# gateway.net
KiCad netlist of a schematic drawn in EAGLE
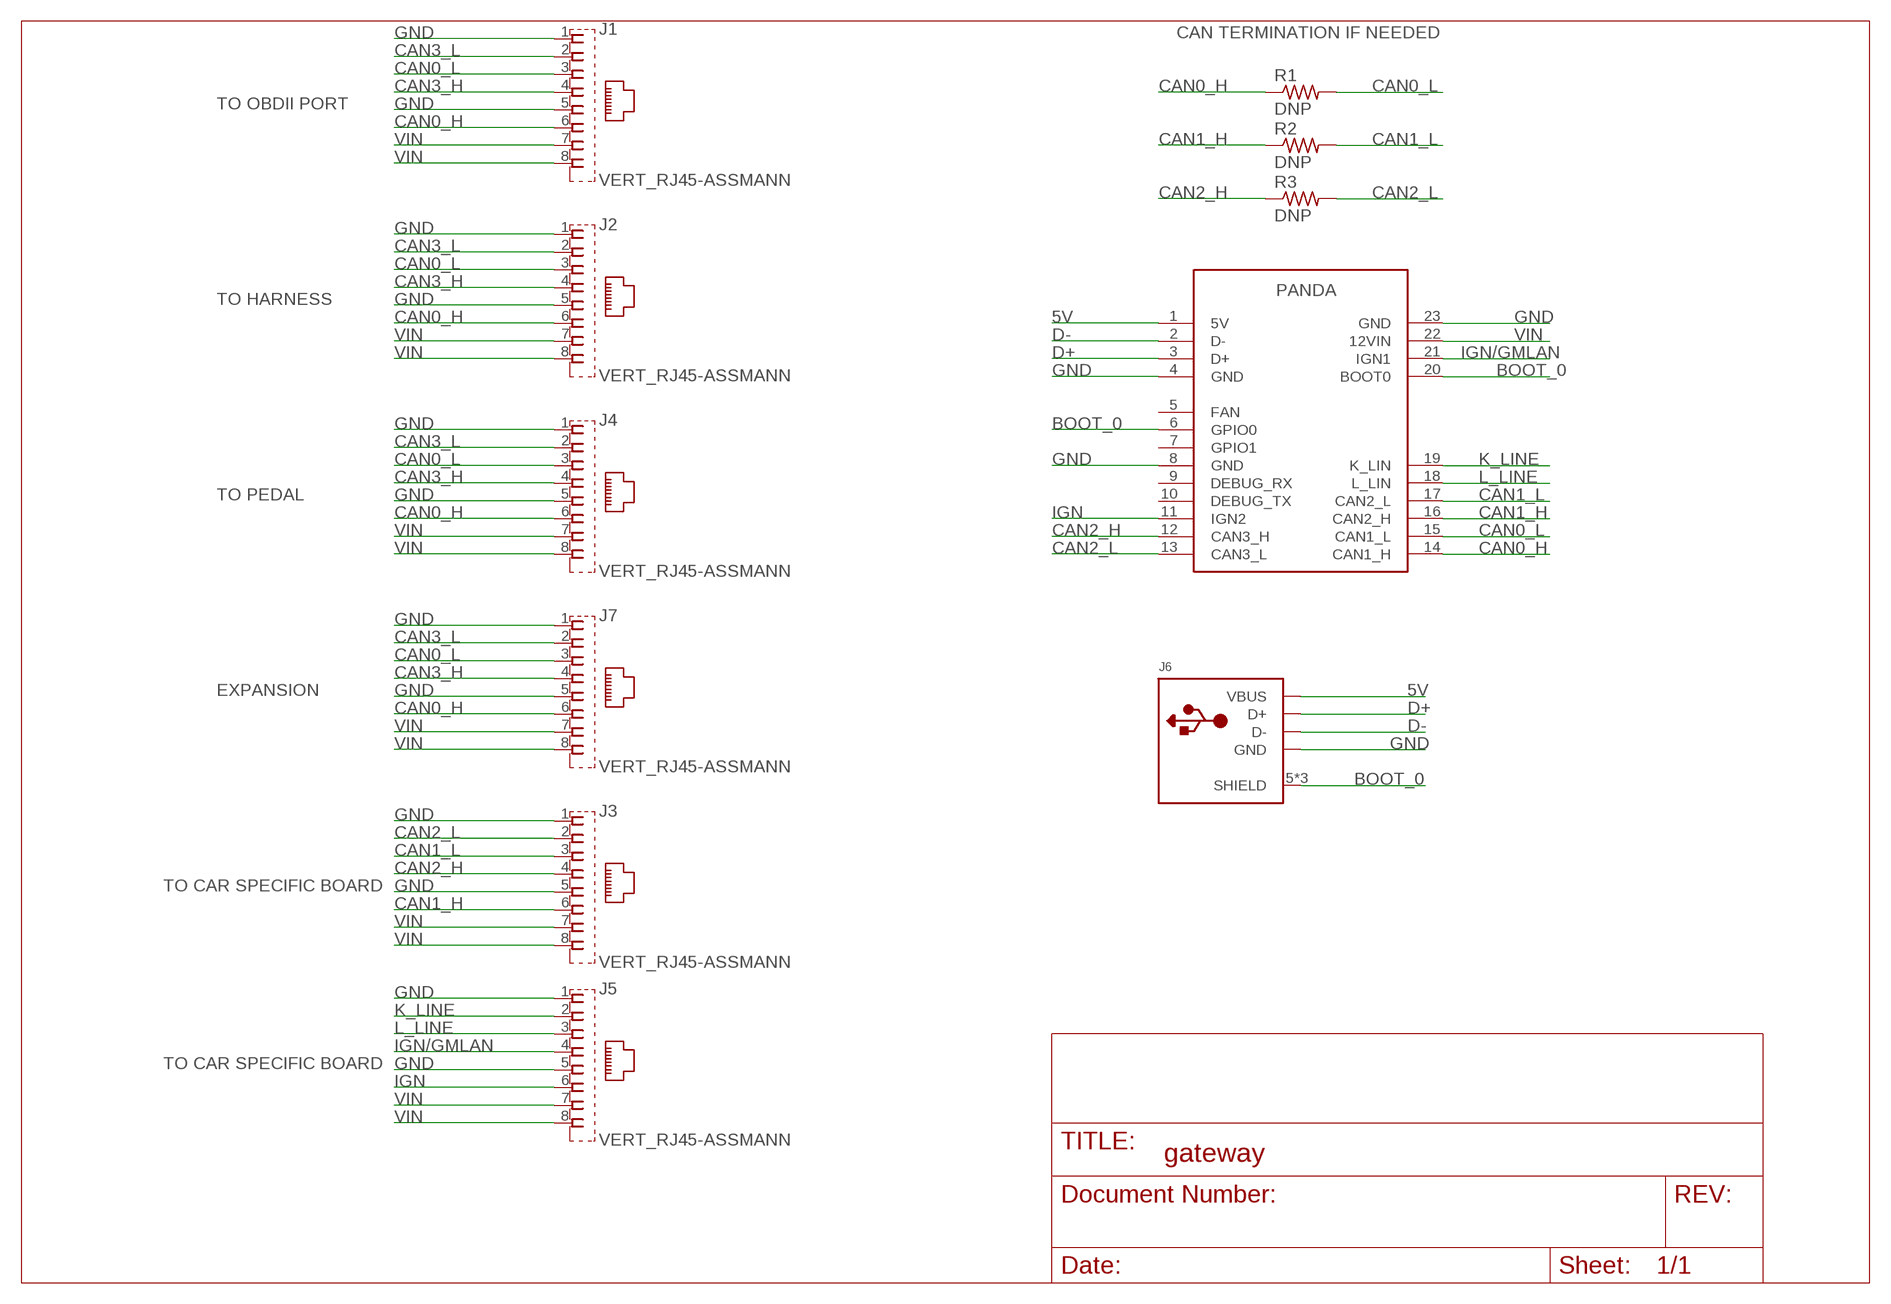
[diagram p0: schematic, sheet 1]

(export (version "E")
  (design (tool "Eeschema 10.0.6"))
  (components
    (comp (ref "J1")
      (value "VERT_RJ45-ASSMANN")
      (footprint "eagle-import:RJ45-VERT")
      (fields (field (name "MPN") "A-2004-2-4-LPS-N-R"))
      (libsource (lib "eagle-import") (part "VERT_RJ45-ASSMANN"))
    )
    (comp (ref "J2")
      (value "VERT_RJ45-ASSMANN")
      (footprint "eagle-import:RJ45-VERT")
      (fields (field (name "MPN") "A-2004-2-4-LPS-N-R"))
      (libsource (lib "eagle-import") (part "VERT_RJ45-ASSMANN"))
    )
    (comp (ref "J3")
      (value "VERT_RJ45-ASSMANN")
      (footprint "eagle-import:RJ45-VERT")
      (fields (field (name "MPN") "A-2004-2-4-LPS-N-R"))
      (libsource (lib "eagle-import") (part "VERT_RJ45-ASSMANN"))
    )
    (comp (ref "J4")
      (value "VERT_RJ45-ASSMANN")
      (footprint "eagle-import:RJ45-VERT")
      (fields (field (name "MPN") "A-2004-2-4-LPS-N-R"))
      (libsource (lib "eagle-import") (part "VERT_RJ45-ASSMANN"))
    )
    (comp (ref "J5")
      (value "VERT_RJ45-ASSMANN")
      (footprint "eagle-import:RJ45-VERT")
      (fields (field (name "MPN") "A-2004-2-4-LPS-N-R"))
      (libsource (lib "eagle-import") (part "VERT_RJ45-ASSMANN"))
    )
    (comp (ref "J6")
      (value "USB-AMOLEX")
      (footprint "eagle-import:USB-A-VERT-MOLEX")
      (fields (field (name "MPN") "1050570001"))
      (libsource (lib "eagle-import") (part "USB-AMOLEX"))
    )
    (comp (ref "J7")
      (value "VERT_RJ45-ASSMANN")
      (footprint "eagle-import:RJ45-VERT")
      (fields (field (name "MPN") "A-2004-2-4-LPS-N-R"))
      (libsource (lib "eagle-import") (part "VERT_RJ45-ASSMANN"))
    )
    (comp (ref "R1")
      (value "DNP")
      (footprint "eagle-import:0603-R")
      (libsource (lib "eagle-import") (part "R0603"))
    )
    (comp (ref "R2")
      (value "DNP")
      (footprint "eagle-import:0603-R")
      (libsource (lib "eagle-import") (part "R0603"))
    )
    (comp (ref "R3")
      (value "DNP")
      (footprint "eagle-import:0603-R")
      (libsource (lib "eagle-import") (part "R0603"))
    )
    (comp (ref "U$1")
      (value "PANDA")
      (footprint "eagle-import:PANDA-FOOT")
      (libsource (lib "eagle-import") (part "PANDA"))
    )
  )
  (nets
    (net (code "1") (name "/5V") (class "Default")
      (node (ref "J6") (pin "1") (pinfunction "VBUS_1") (pintype "power_in"))
      (node (ref "U$1") (pin "1") (pinfunction "5V_1") (pintype "bidirectional"))
    )
    (net (code "2") (name "/BOOT_0") (class "Default")
      (node (ref "J6") (pin "5") (pinfunction "SHIELD_5") (pintype "bidirectional"))
      (node (ref "J6") (pin "6") (pinfunction "SHIELD_6") (pintype "bidirectional"))
      (node (ref "J6") (pin "7") (pinfunction "SHIELD_7") (pintype "bidirectional"))
      (node (ref "U$1") (pin "20") (pinfunction "BOOT0_20") (pintype "bidirectional"))
      (node (ref "U$1") (pin "6") (pinfunction "GPIO0_6") (pintype "bidirectional"))
    )
    (net (code "3") (name "/CAN0_H") (class "Default")
      (node (ref "J1") (pin "6") (pinfunction "6_6") (pintype "passive"))
      (node (ref "J2") (pin "6") (pinfunction "6_6") (pintype "passive"))
      (node (ref "J4") (pin "6") (pinfunction "6_6") (pintype "passive"))
      (node (ref "J7") (pin "6") (pinfunction "6_6") (pintype "passive"))
      (node (ref "R1") (pin "1") (pinfunction "1_1") (pintype "passive"))
      (node (ref "U$1") (pin "14") (pinfunction "CAN1_H_14") (pintype "bidirectional"))
    )
    (net (code "4") (name "/CAN0_L") (class "Default")
      (node (ref "J1") (pin "3") (pinfunction "3_3") (pintype "passive"))
      (node (ref "J2") (pin "3") (pinfunction "3_3") (pintype "passive"))
      (node (ref "J4") (pin "3") (pinfunction "3_3") (pintype "passive"))
      (node (ref "J7") (pin "3") (pinfunction "3_3") (pintype "passive"))
      (node (ref "R1") (pin "2") (pinfunction "2_2") (pintype "passive"))
      (node (ref "U$1") (pin "15") (pinfunction "CAN1_L_15") (pintype "bidirectional"))
    )
    (net (code "5") (name "/CAN1_H") (class "Default")
      (node (ref "J3") (pin "6") (pinfunction "6_6") (pintype "passive"))
      (node (ref "R2") (pin "1") (pinfunction "1_1") (pintype "passive"))
      (node (ref "U$1") (pin "16") (pinfunction "CAN2_H_16") (pintype "bidirectional"))
    )
    (net (code "6") (name "/CAN1_L") (class "Default")
      (node (ref "J3") (pin "3") (pinfunction "3_3") (pintype "passive"))
      (node (ref "R2") (pin "2") (pinfunction "2_2") (pintype "passive"))
      (node (ref "U$1") (pin "17") (pinfunction "CAN2_L_17") (pintype "bidirectional"))
    )
    (net (code "7") (name "/CAN2_H") (class "Default")
      (node (ref "J3") (pin "4") (pinfunction "4_4") (pintype "passive"))
      (node (ref "R3") (pin "1") (pinfunction "1_1") (pintype "passive"))
      (node (ref "U$1") (pin "12") (pinfunction "CAN3_H_12") (pintype "bidirectional"))
    )
    (net (code "8") (name "/CAN2_L") (class "Default")
      (node (ref "J3") (pin "2") (pinfunction "2_2") (pintype "passive"))
      (node (ref "R3") (pin "2") (pinfunction "2_2") (pintype "passive"))
      (node (ref "U$1") (pin "13") (pinfunction "CAN3_L_13") (pintype "bidirectional"))
    )
    (net (code "9") (name "/CAN3_H") (class "Default")
      (node (ref "J1") (pin "4") (pinfunction "4_4") (pintype "passive"))
      (node (ref "J2") (pin "4") (pinfunction "4_4") (pintype "passive"))
      (node (ref "J4") (pin "4") (pinfunction "4_4") (pintype "passive"))
      (node (ref "J7") (pin "4") (pinfunction "4_4") (pintype "passive"))
    )
    (net (code "10") (name "/CAN3_L") (class "Default")
      (node (ref "J1") (pin "2") (pinfunction "2_2") (pintype "passive"))
      (node (ref "J2") (pin "2") (pinfunction "2_2") (pintype "passive"))
      (node (ref "J4") (pin "2") (pinfunction "2_2") (pintype "passive"))
      (node (ref "J7") (pin "2") (pinfunction "2_2") (pintype "passive"))
    )
    (net (code "11") (name "/D+") (class "Default")
      (node (ref "J6") (pin "3") (pinfunction "D+_3") (pintype "bidirectional"))
      (node (ref "U$1") (pin "3") (pinfunction "D+_3") (pintype "bidirectional"))
    )
    (net (code "12") (name "/D-") (class "Default")
      (node (ref "J6") (pin "2") (pinfunction "D-_2") (pintype "bidirectional"))
      (node (ref "U$1") (pin "2") (pinfunction "D-_2") (pintype "bidirectional"))
    )
    (net (code "13") (name "/GND") (class "Default")
      (node (ref "J1") (pin "1") (pinfunction "1_1") (pintype "passive"))
      (node (ref "J1") (pin "5") (pinfunction "5_5") (pintype "passive"))
      (node (ref "J2") (pin "1") (pinfunction "1_1") (pintype "passive"))
      (node (ref "J2") (pin "5") (pinfunction "5_5") (pintype "passive"))
      (node (ref "J3") (pin "1") (pinfunction "1_1") (pintype "passive"))
      (node (ref "J3") (pin "5") (pinfunction "5_5") (pintype "passive"))
      (node (ref "J4") (pin "1") (pinfunction "1_1") (pintype "passive"))
      (node (ref "J4") (pin "5") (pinfunction "5_5") (pintype "passive"))
      (node (ref "J5") (pin "1") (pinfunction "1_1") (pintype "passive"))
      (node (ref "J5") (pin "5") (pinfunction "5_5") (pintype "passive"))
      (node (ref "J6") (pin "4") (pinfunction "GND_4") (pintype "power_in"))
      (node (ref "J7") (pin "1") (pinfunction "1_1") (pintype "passive"))
      (node (ref "J7") (pin "5") (pinfunction "5_5") (pintype "passive"))
      (node (ref "U$1") (pin "23") (pinfunction "GND_23") (pintype "bidirectional"))
      (node (ref "U$1") (pin "4") (pinfunction "GND_4") (pintype "bidirectional"))
      (node (ref "U$1") (pin "8") (pinfunction "GND_8") (pintype "bidirectional"))
    )
    (net (code "14") (name "/IGN") (class "Default")
      (node (ref "J5") (pin "6") (pinfunction "6_6") (pintype "passive"))
      (node (ref "U$1") (pin "11") (pinfunction "IGN2_11") (pintype "bidirectional"))
    )
    (net (code "15") (name "/IGN{slash}GMLAN") (class "Default")
      (node (ref "J5") (pin "4") (pinfunction "4_4") (pintype "passive"))
      (node (ref "U$1") (pin "21") (pinfunction "IGN1_21") (pintype "bidirectional"))
    )
    (net (code "16") (name "/K_LINE") (class "Default")
      (node (ref "J5") (pin "2") (pinfunction "2_2") (pintype "passive"))
      (node (ref "U$1") (pin "19") (pinfunction "K_LIN_19") (pintype "bidirectional"))
    )
    (net (code "17") (name "/L_LINE") (class "Default")
      (node (ref "J5") (pin "3") (pinfunction "3_3") (pintype "passive"))
      (node (ref "U$1") (pin "18") (pinfunction "L_LIN_18") (pintype "bidirectional"))
    )
    (net (code "18") (name "/VIN") (class "Default")
      (node (ref "J1") (pin "7") (pinfunction "7_7") (pintype "passive"))
      (node (ref "J1") (pin "8") (pinfunction "8_8") (pintype "passive"))
      (node (ref "J2") (pin "7") (pinfunction "7_7") (pintype "passive"))
      (node (ref "J2") (pin "8") (pinfunction "8_8") (pintype "passive"))
      (node (ref "J3") (pin "7") (pinfunction "7_7") (pintype "passive"))
      (node (ref "J3") (pin "8") (pinfunction "8_8") (pintype "passive"))
      (node (ref "J4") (pin "7") (pinfunction "7_7") (pintype "passive"))
      (node (ref "J4") (pin "8") (pinfunction "8_8") (pintype "passive"))
      (node (ref "J5") (pin "7") (pinfunction "7_7") (pintype "passive"))
      (node (ref "J5") (pin "8") (pinfunction "8_8") (pintype "passive"))
      (node (ref "J7") (pin "7") (pinfunction "7_7") (pintype "passive"))
      (node (ref "J7") (pin "8") (pinfunction "8_8") (pintype "passive"))
      (node (ref "U$1") (pin "22") (pinfunction "12VIN_22") (pintype "bidirectional"))
    )
    (net (code "19") (name "unconnected-(U$1-DEBUG_RX-Pad9)") (class "Default")
      (node (ref "U$1") (pin "9") (pinfunction "DEBUG_RX_9") (pintype "bidirectional"))
    )
    (net (code "20") (name "unconnected-(U$1-DEBUG_TX-Pad10)") (class "Default")
      (node (ref "U$1") (pin "10") (pinfunction "DEBUG_TX_10") (pintype "bidirectional"))
    )
    (net (code "21") (name "unconnected-(U$1-FAN-Pad5)") (class "Default")
      (node (ref "U$1") (pin "5") (pinfunction "FAN_5") (pintype "bidirectional"))
    )
    (net (code "22") (name "unconnected-(U$1-GPIO1-Pad7)") (class "Default")
      (node (ref "U$1") (pin "7") (pinfunction "GPIO1_7") (pintype "bidirectional"))
    )
  )
)
